# MakerBot.net
KiCad netlist of a schematic drawn in EAGLE
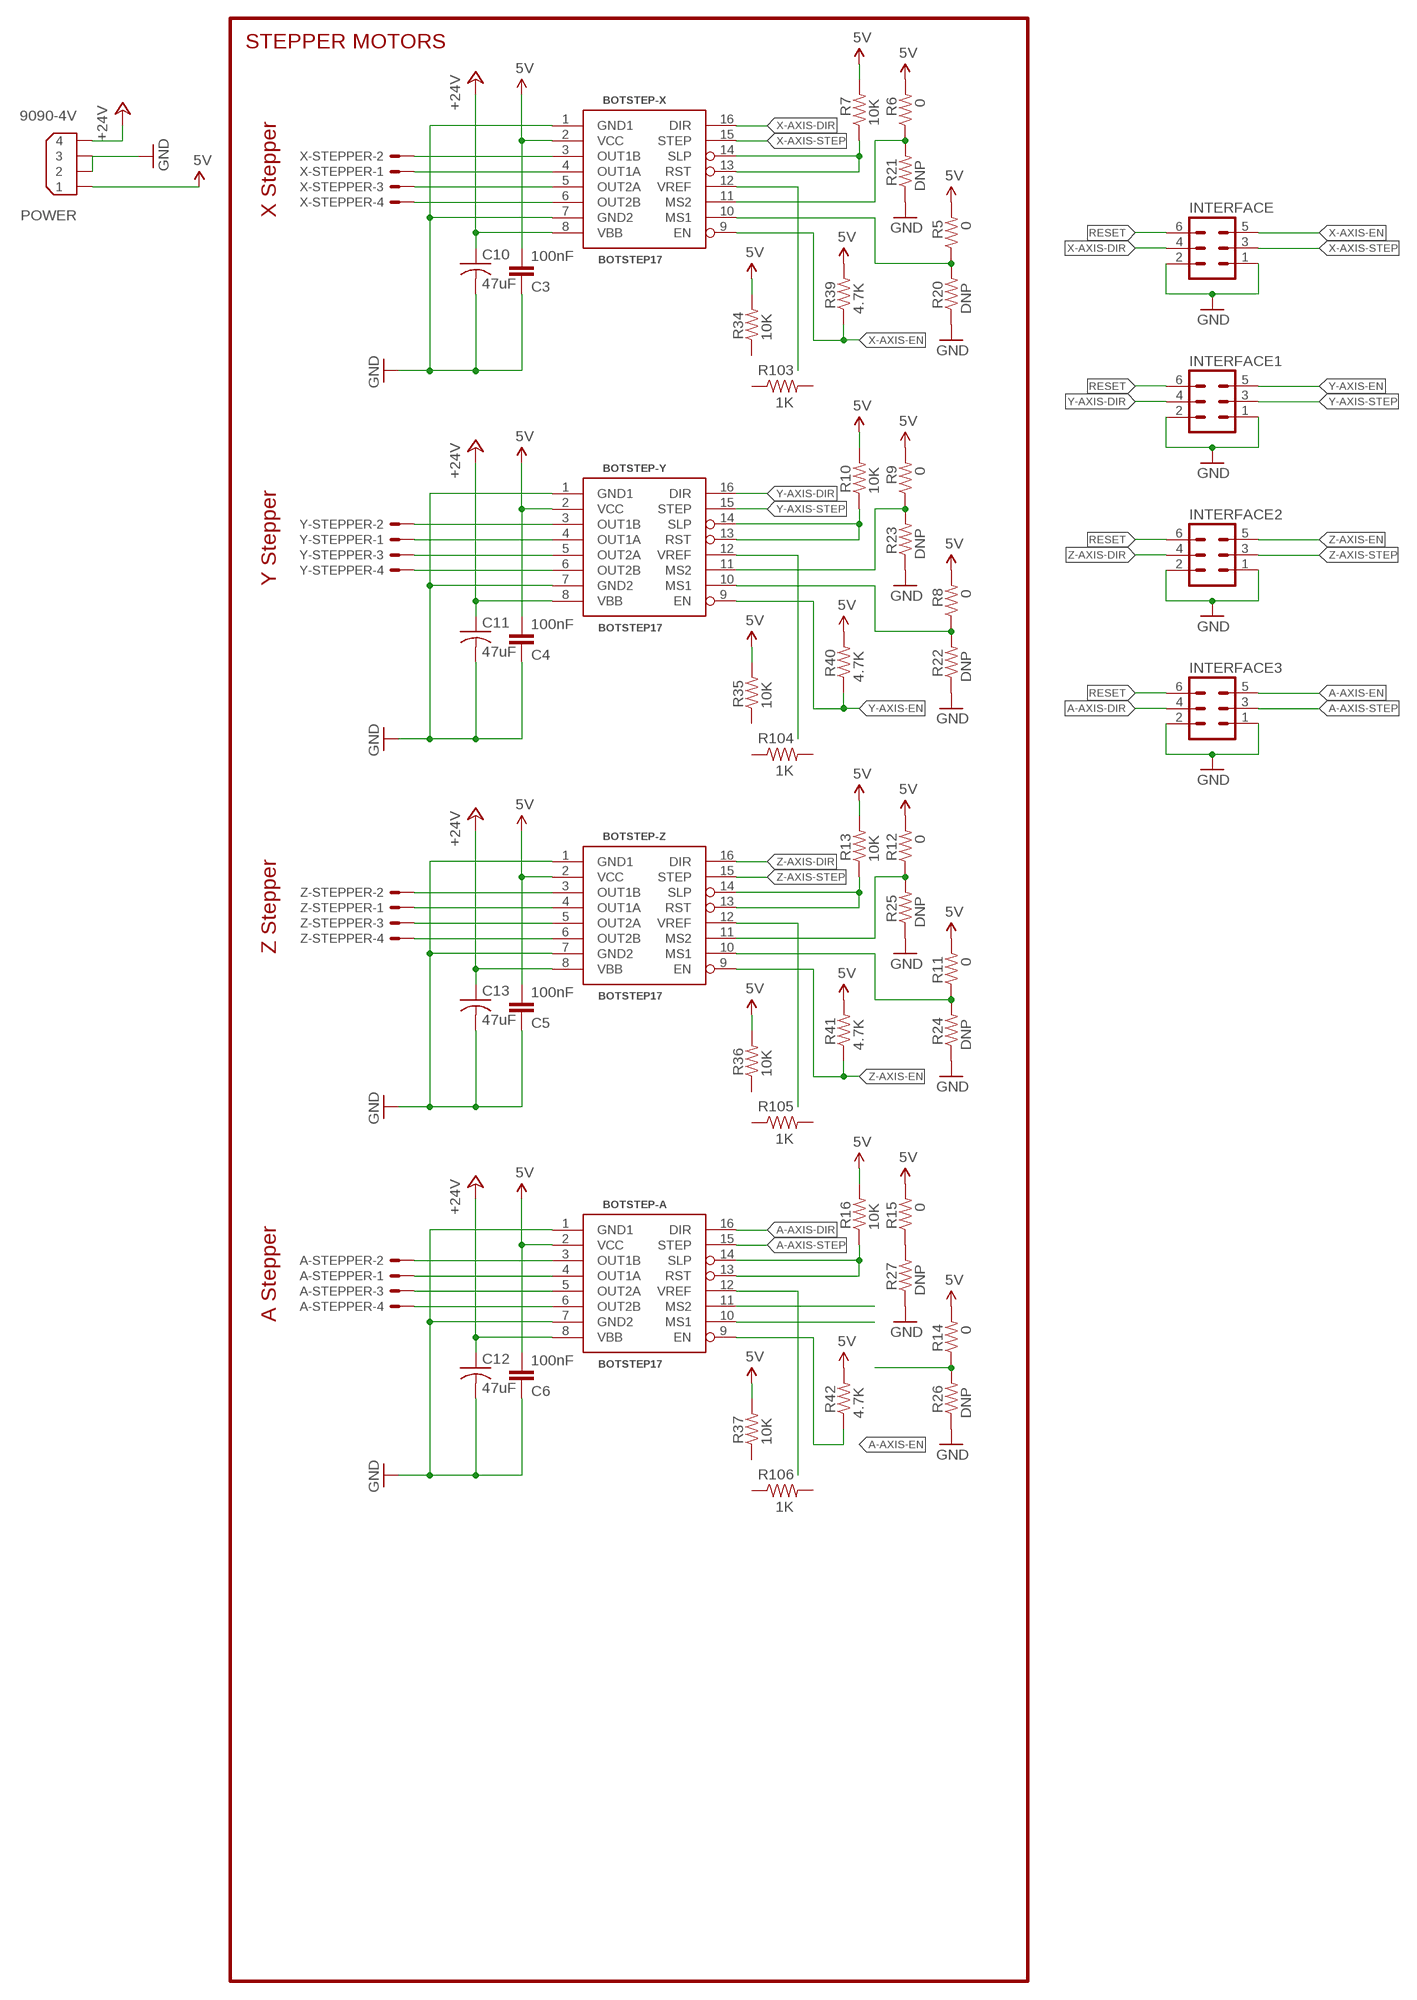
[diagram p0: schematic, sheet 1]

(export (version "E")
  (design (tool "Eeschema 10.0.6"))
  (components
    (comp (ref "A-STEPPER")
      (value "KK-156-4")
      (footprint "eagle-import:KK-156-4")
      (libsource (lib "eagle-import") (part "KK-156-4"))
    )
    (comp (ref "BOTSTEP-A")
      (value "BOTSTEP17")
      (footprint "eagle-import:BOTSTEP17-INV")
      (libsource (lib "eagle-import") (part "BOTSTEP17CHIP-DOWN"))
    )
    (comp (ref "BOTSTEP-X")
      (value "BOTSTEP17")
      (footprint "eagle-import:BOTSTEP17-INV")
      (libsource (lib "eagle-import") (part "BOTSTEP17CHIP-DOWN"))
    )
    (comp (ref "BOTSTEP-Y")
      (value "BOTSTEP17")
      (footprint "eagle-import:BOTSTEP17-INV")
      (libsource (lib "eagle-import") (part "BOTSTEP17CHIP-DOWN"))
    )
    (comp (ref "BOTSTEP-Z")
      (value "BOTSTEP17")
      (footprint "eagle-import:BOTSTEP17-INV")
      (libsource (lib "eagle-import") (part "BOTSTEP17CHIP-DOWN"))
    )
    (comp (ref "C3")
      (value "100nF")
      (footprint "eagle-import:0805")
      (libsource (lib "eagle-import") (part "CAP0805"))
    )
    (comp (ref "C4")
      (value "100nF")
      (footprint "eagle-import:0805")
      (libsource (lib "eagle-import") (part "CAP0805"))
    )
    (comp (ref "C5")
      (value "100nF")
      (footprint "eagle-import:0805")
      (libsource (lib "eagle-import") (part "CAP0805"))
    )
    (comp (ref "C6")
      (value "100nF")
      (footprint "eagle-import:0805")
      (libsource (lib "eagle-import") (part "CAP0805"))
    )
    (comp (ref "C10")
      (value "47uF")
      (footprint "eagle-import:C050-075X075")
      (libsource (lib "eagle-import") (part "C-US050-075X075"))
    )
    (comp (ref "C11")
      (value "47uF")
      (footprint "eagle-import:C050-075X075")
      (libsource (lib "eagle-import") (part "C-US050-075X075"))
    )
    (comp (ref "C12")
      (value "47uF")
      (footprint "eagle-import:C050-075X075")
      (libsource (lib "eagle-import") (part "C-US050-075X075"))
    )
    (comp (ref "C13")
      (value "47uF")
      (footprint "eagle-import:C050-075X075")
      (libsource (lib "eagle-import") (part "C-US050-075X075"))
    )
    (comp (ref "INTERFACE")
      (value "ML6")
      (footprint "eagle-import:ML6")
      (libsource (lib "eagle-import") (part "ML6"))
    )
    (comp (ref "INTERFACE1")
      (value "ML6")
      (footprint "eagle-import:ML6")
      (libsource (lib "eagle-import") (part "ML6"))
    )
    (comp (ref "INTERFACE2")
      (value "ML6")
      (footprint "eagle-import:ML6")
      (libsource (lib "eagle-import") (part "ML6"))
    )
    (comp (ref "INTERFACE3")
      (value "ML6")
      (footprint "eagle-import:ML6")
      (libsource (lib "eagle-import") (part "ML6"))
    )
    (comp (ref "POWER")
      (value "9090-4V")
      (footprint "eagle-import:9090-4V")
      (libsource (lib "eagle-import") (part "9090-4V"))
    )
    (comp (ref "R5")
      (value "0")
      (footprint "eagle-import:AXIAL-0.3")
      (libsource (lib "eagle-import") (part "RESISTORPTH1"))
    )
    (comp (ref "R6")
      (value "0")
      (footprint "eagle-import:AXIAL-0.3")
      (libsource (lib "eagle-import") (part "RESISTORPTH1"))
    )
    (comp (ref "R7")
      (value "10K")
      (footprint "eagle-import:AXIAL-0.3")
      (libsource (lib "eagle-import") (part "RESISTORPTH1"))
    )
    (comp (ref "R8")
      (value "0")
      (footprint "eagle-import:AXIAL-0.3")
      (libsource (lib "eagle-import") (part "RESISTORPTH1"))
    )
    (comp (ref "R9")
      (value "0")
      (footprint "eagle-import:AXIAL-0.3")
      (libsource (lib "eagle-import") (part "RESISTORPTH1"))
    )
    (comp (ref "R10")
      (value "10K")
      (footprint "eagle-import:AXIAL-0.3")
      (libsource (lib "eagle-import") (part "RESISTORPTH1"))
    )
    (comp (ref "R11")
      (value "0")
      (footprint "eagle-import:0805")
      (libsource (lib "eagle-import") (part "RESISTOR"))
    )
    (comp (ref "R12")
      (value "0")
      (footprint "eagle-import:0805")
      (libsource (lib "eagle-import") (part "RESISTOR"))
    )
    (comp (ref "R13")
      (value "10K")
      (footprint "eagle-import:0805")
      (libsource (lib "eagle-import") (part "RESISTOR"))
    )
    (comp (ref "R14")
      (value "0")
      (footprint "eagle-import:0805")
      (libsource (lib "eagle-import") (part "RESISTOR"))
    )
    (comp (ref "R15")
      (value "0")
      (footprint "eagle-import:0805")
      (libsource (lib "eagle-import") (part "RESISTOR"))
    )
    (comp (ref "R16")
      (value "10K")
      (footprint "eagle-import:0805")
      (libsource (lib "eagle-import") (part "RESISTOR"))
    )
    (comp (ref "R20")
      (value "DNP")
      (footprint "eagle-import:AXIAL-0.3")
      (libsource (lib "eagle-import") (part "RESISTORPTH1"))
    )
    (comp (ref "R21")
      (value "DNP")
      (footprint "eagle-import:AXIAL-0.3")
      (libsource (lib "eagle-import") (part "RESISTORPTH1"))
    )
    (comp (ref "R22")
      (value "DNP")
      (footprint "eagle-import:AXIAL-0.3")
      (libsource (lib "eagle-import") (part "RESISTORPTH1"))
    )
    (comp (ref "R23")
      (value "DNP")
      (footprint "eagle-import:AXIAL-0.3")
      (libsource (lib "eagle-import") (part "RESISTORPTH1"))
    )
    (comp (ref "R24")
      (value "DNP")
      (footprint "eagle-import:0805")
      (libsource (lib "eagle-import") (part "RESISTOR"))
    )
    (comp (ref "R25")
      (value "DNP")
      (footprint "eagle-import:0805")
      (libsource (lib "eagle-import") (part "RESISTOR"))
    )
    (comp (ref "R26")
      (value "DNP")
      (footprint "eagle-import:0805")
      (libsource (lib "eagle-import") (part "RESISTOR"))
    )
    (comp (ref "R27")
      (value "DNP")
      (footprint "eagle-import:0805")
      (libsource (lib "eagle-import") (part "RESISTOR"))
    )
    (comp (ref "R34")
      (value "10K")
      (footprint "eagle-import:AXIAL-0.3")
      (libsource (lib "eagle-import") (part "RESISTORPTH1"))
    )
    (comp (ref "R35")
      (value "10K")
      (footprint "eagle-import:AXIAL-0.3")
      (libsource (lib "eagle-import") (part "RESISTORPTH1"))
    )
    (comp (ref "R36")
      (value "10K")
      (footprint "eagle-import:0805")
      (libsource (lib "eagle-import") (part "RESISTOR"))
    )
    (comp (ref "R37")
      (value "10K")
      (footprint "eagle-import:0805")
      (libsource (lib "eagle-import") (part "RESISTOR"))
    )
    (comp (ref "R39")
      (value "4.7K")
      (footprint "eagle-import:AXIAL-0.3")
      (libsource (lib "eagle-import") (part "RESISTORPTH1"))
    )
    (comp (ref "R40")
      (value "4.7K")
      (footprint "eagle-import:AXIAL-0.3")
      (libsource (lib "eagle-import") (part "RESISTORPTH1"))
    )
    (comp (ref "R41")
      (value "4.7K")
      (footprint "eagle-import:0805")
      (libsource (lib "eagle-import") (part "RESISTOR"))
    )
    (comp (ref "R42")
      (value "4.7K")
      (footprint "eagle-import:0805")
      (libsource (lib "eagle-import") (part "RESISTOR"))
    )
    (comp (ref "R103")
      (value "1K")
      (footprint "eagle-import:AXIAL-0.3")
      (libsource (lib "eagle-import") (part "RESISTORPTH1"))
    )
    (comp (ref "R104")
      (value "1K")
      (footprint "eagle-import:AXIAL-0.3")
      (libsource (lib "eagle-import") (part "RESISTORPTH1"))
    )
    (comp (ref "R105")
      (value "1K")
      (footprint "eagle-import:0805")
      (libsource (lib "eagle-import") (part "RESISTOR"))
    )
    (comp (ref "R106")
      (value "1K")
      (footprint "eagle-import:0805")
      (libsource (lib "eagle-import") (part "RESISTOR"))
    )
    (comp (ref "X-STEPPER")
      (value "KK-156-4")
      (footprint "eagle-import:KK-156-4")
      (libsource (lib "eagle-import") (part "KK-156-4"))
    )
    (comp (ref "Y-STEPPER")
      (value "KK-156-4")
      (footprint "eagle-import:KK-156-4")
      (libsource (lib "eagle-import") (part "KK-156-4"))
    )
    (comp (ref "Z-STEPPER")
      (value "KK-156-4")
      (footprint "eagle-import:KK-156-4")
      (libsource (lib "eagle-import") (part "KK-156-4"))
    )
  )
  (nets
    (net (code "1") (name "+24V") (class "Default")
      (node (ref "BOTSTEP-A") (pin "8") (pinfunction "VBB_8") (pintype "bidirectional"))
      (node (ref "BOTSTEP-X") (pin "8") (pinfunction "VBB_8") (pintype "bidirectional"))
      (node (ref "BOTSTEP-Y") (pin "8") (pinfunction "VBB_8") (pintype "bidirectional"))
      (node (ref "BOTSTEP-Z") (pin "8") (pinfunction "VBB_8") (pintype "bidirectional"))
      (node (ref "C10") (pin "1") (pinfunction "1_1") (pintype "passive"))
      (node (ref "C11") (pin "1") (pinfunction "1_1") (pintype "passive"))
      (node (ref "C12") (pin "1") (pinfunction "1_1") (pintype "passive"))
      (node (ref "C13") (pin "1") (pinfunction "1_1") (pintype "passive"))
      (node (ref "POWER") (pin "4") (pinfunction "4_4") (pintype "passive"))
    )
    (net (code "2") (name "5V") (class "Default")
      (node (ref "BOTSTEP-A") (pin "2") (pinfunction "VCC_2") (pintype "bidirectional"))
      (node (ref "BOTSTEP-X") (pin "2") (pinfunction "VCC_2") (pintype "bidirectional"))
      (node (ref "BOTSTEP-Y") (pin "2") (pinfunction "VCC_2") (pintype "bidirectional"))
      (node (ref "BOTSTEP-Z") (pin "2") (pinfunction "VCC_2") (pintype "bidirectional"))
      (node (ref "C3") (pin "2") (pinfunction "2_2") (pintype "passive"))
      (node (ref "C4") (pin "2") (pinfunction "2_2") (pintype "passive"))
      (node (ref "C5") (pin "2") (pinfunction "2_2") (pintype "passive"))
      (node (ref "C6") (pin "2") (pinfunction "2_2") (pintype "passive"))
      (node (ref "POWER") (pin "1") (pinfunction "1_1") (pintype "passive"))
      (node (ref "R10") (pin "P$2") (pinfunction "2_P$2") (pintype "passive"))
      (node (ref "R11") (pin "2") (pinfunction "2_2") (pintype "passive"))
      (node (ref "R12") (pin "2") (pinfunction "2_2") (pintype "passive"))
      (node (ref "R13") (pin "2") (pinfunction "2_2") (pintype "passive"))
      (node (ref "R14") (pin "2") (pinfunction "2_2") (pintype "passive"))
      (node (ref "R15") (pin "2") (pinfunction "2_2") (pintype "passive"))
      (node (ref "R16") (pin "2") (pinfunction "2_2") (pintype "passive"))
      (node (ref "R34") (pin "P$2") (pinfunction "2_P$2") (pintype "passive"))
      (node (ref "R35") (pin "P$2") (pinfunction "2_P$2") (pintype "passive"))
      (node (ref "R36") (pin "2") (pinfunction "2_2") (pintype "passive"))
      (node (ref "R37") (pin "2") (pinfunction "2_2") (pintype "passive"))
      (node (ref "R39") (pin "P$2") (pinfunction "2_P$2") (pintype "passive"))
      (node (ref "R40") (pin "P$2") (pinfunction "2_P$2") (pintype "passive"))
      (node (ref "R41") (pin "2") (pinfunction "2_2") (pintype "passive"))
      (node (ref "R42") (pin "2") (pinfunction "2_2") (pintype "passive"))
      (node (ref "R5") (pin "P$2") (pinfunction "2_P$2") (pintype "passive"))
      (node (ref "R6") (pin "P$2") (pinfunction "2_P$2") (pintype "passive"))
      (node (ref "R7") (pin "P$2") (pinfunction "2_P$2") (pintype "passive"))
      (node (ref "R8") (pin "P$2") (pinfunction "2_P$2") (pintype "passive"))
      (node (ref "R9") (pin "P$2") (pinfunction "2_P$2") (pintype "passive"))
    )
    (net (code "3") (name "A-AXIS-DIR") (class "Default")
      (node (ref "BOTSTEP-A") (pin "16") (pinfunction "DIR_16") (pintype "input"))
      (node (ref "INTERFACE3") (pin "4") (pinfunction "4_4") (pintype "passive"))
    )
    (net (code "4") (name "A-AXIS-EN") (class "Default")
      (node (ref "BOTSTEP-A") (pin "9") (pinfunction "EN_9") (pintype "input"))
      (node (ref "INTERFACE3") (pin "5") (pinfunction "5_5") (pintype "passive"))
      (node (ref "R42") (pin "1") (pinfunction "1_1") (pintype "passive"))
    )
    (net (code "5") (name "A-AXIS-STEP") (class "Default")
      (node (ref "BOTSTEP-A") (pin "15") (pinfunction "STEP_15") (pintype "input"))
      (node (ref "INTERFACE3") (pin "3") (pinfunction "3_3") (pintype "passive"))
    )
    (net (code "6") (name "GND") (class "Default")
      (node (ref "BOTSTEP-A") (pin "1") (pinfunction "GND1_1") (pintype "bidirectional"))
      (node (ref "BOTSTEP-A") (pin "7") (pinfunction "GND2_7") (pintype "bidirectional"))
      (node (ref "BOTSTEP-X") (pin "1") (pinfunction "GND1_1") (pintype "bidirectional"))
      (node (ref "BOTSTEP-X") (pin "7") (pinfunction "GND2_7") (pintype "bidirectional"))
      (node (ref "BOTSTEP-Y") (pin "1") (pinfunction "GND1_1") (pintype "bidirectional"))
      (node (ref "BOTSTEP-Y") (pin "7") (pinfunction "GND2_7") (pintype "bidirectional"))
      (node (ref "BOTSTEP-Z") (pin "1") (pinfunction "GND1_1") (pintype "bidirectional"))
      (node (ref "BOTSTEP-Z") (pin "7") (pinfunction "GND2_7") (pintype "bidirectional"))
      (node (ref "C10") (pin "2") (pinfunction "2_2") (pintype "passive"))
      (node (ref "C11") (pin "2") (pinfunction "2_2") (pintype "passive"))
      (node (ref "C12") (pin "2") (pinfunction "2_2") (pintype "passive"))
      (node (ref "C13") (pin "2") (pinfunction "2_2") (pintype "passive"))
      (node (ref "C3") (pin "1") (pinfunction "1_1") (pintype "passive"))
      (node (ref "C4") (pin "1") (pinfunction "1_1") (pintype "passive"))
      (node (ref "C5") (pin "1") (pinfunction "1_1") (pintype "passive"))
      (node (ref "C6") (pin "1") (pinfunction "1_1") (pintype "passive"))
      (node (ref "INTERFACE") (pin "1") (pinfunction "1_1") (pintype "passive"))
      (node (ref "INTERFACE") (pin "2") (pinfunction "2_2") (pintype "passive"))
      (node (ref "INTERFACE1") (pin "1") (pinfunction "1_1") (pintype "passive"))
      (node (ref "INTERFACE1") (pin "2") (pinfunction "2_2") (pintype "passive"))
      (node (ref "INTERFACE2") (pin "1") (pinfunction "1_1") (pintype "passive"))
      (node (ref "INTERFACE2") (pin "2") (pinfunction "2_2") (pintype "passive"))
      (node (ref "INTERFACE3") (pin "1") (pinfunction "1_1") (pintype "passive"))
      (node (ref "INTERFACE3") (pin "2") (pinfunction "2_2") (pintype "passive"))
      (node (ref "POWER") (pin "2") (pinfunction "2_2") (pintype "passive"))
      (node (ref "POWER") (pin "3") (pinfunction "3_3") (pintype "passive"))
      (node (ref "R20") (pin "P$1") (pinfunction "1_P$1") (pintype "passive"))
      (node (ref "R21") (pin "P$1") (pinfunction "1_P$1") (pintype "passive"))
      (node (ref "R22") (pin "P$1") (pinfunction "1_P$1") (pintype "passive"))
      (node (ref "R23") (pin "P$1") (pinfunction "1_P$1") (pintype "passive"))
      (node (ref "R24") (pin "1") (pinfunction "1_1") (pintype "passive"))
      (node (ref "R25") (pin "1") (pinfunction "1_1") (pintype "passive"))
      (node (ref "R26") (pin "1") (pinfunction "1_1") (pintype "passive"))
      (node (ref "R27") (pin "1") (pinfunction "1_1") (pintype "passive"))
    )
    (net (code "7") (name "Net-(A-STEPPERA-S)") (class "Default")
      (node (ref "A-STEPPER") (pin "1") (pinfunction "S_1") (pintype "passive"))
      (node (ref "BOTSTEP-A") (pin "4") (pinfunction "OUT1A_4") (pintype "output"))
    )
    (net (code "8") (name "Net-(A-STEPPERB-S)") (class "Default")
      (node (ref "A-STEPPER") (pin "2") (pinfunction "S_2") (pintype "passive"))
      (node (ref "BOTSTEP-A") (pin "3") (pinfunction "OUT1B_3") (pintype "output"))
    )
    (net (code "9") (name "Net-(A-STEPPERC-S)") (class "Default")
      (node (ref "A-STEPPER") (pin "3") (pinfunction "S_3") (pintype "passive"))
      (node (ref "BOTSTEP-A") (pin "5") (pinfunction "OUT2A_5") (pintype "output"))
    )
    (net (code "10") (name "Net-(A-STEPPERD-S)") (class "Default")
      (node (ref "A-STEPPER") (pin "4") (pinfunction "S_4") (pintype "passive"))
      (node (ref "BOTSTEP-A") (pin "6") (pinfunction "OUT2B_6") (pintype "output"))
    )
    (net (code "11") (name "Net-(BOTSTEP-A-RST)") (class "Default")
      (node (ref "BOTSTEP-A") (pin "13") (pinfunction "RST_13") (pintype "input"))
      (node (ref "BOTSTEP-A") (pin "14") (pinfunction "SLP_14") (pintype "input"))
      (node (ref "R16") (pin "1") (pinfunction "1_1") (pintype "passive"))
    )
    (net (code "12") (name "Net-(BOTSTEP-X-MS1)") (class "Default")
      (node (ref "BOTSTEP-X") (pin "10") (pinfunction "MS1_10") (pintype "input"))
      (node (ref "R20") (pin "P$2") (pinfunction "2_P$2") (pintype "passive"))
      (node (ref "R5") (pin "P$1") (pinfunction "1_P$1") (pintype "passive"))
    )
    (net (code "13") (name "Net-(BOTSTEP-X-MS2)") (class "Default")
      (node (ref "BOTSTEP-X") (pin "11") (pinfunction "MS2_11") (pintype "input"))
      (node (ref "R21") (pin "P$2") (pinfunction "2_P$2") (pintype "passive"))
      (node (ref "R6") (pin "P$1") (pinfunction "1_P$1") (pintype "passive"))
    )
    (net (code "14") (name "Net-(BOTSTEP-X-OUT1A)") (class "Default")
      (node (ref "BOTSTEP-X") (pin "4") (pinfunction "OUT1A_4") (pintype "output"))
      (node (ref "X-STEPPER") (pin "1") (pinfunction "S_1") (pintype "passive"))
    )
    (net (code "15") (name "Net-(BOTSTEP-X-OUT1B)") (class "Default")
      (node (ref "BOTSTEP-X") (pin "3") (pinfunction "OUT1B_3") (pintype "output"))
      (node (ref "X-STEPPER") (pin "2") (pinfunction "S_2") (pintype "passive"))
    )
    (net (code "16") (name "Net-(BOTSTEP-X-OUT2A)") (class "Default")
      (node (ref "BOTSTEP-X") (pin "5") (pinfunction "OUT2A_5") (pintype "output"))
      (node (ref "X-STEPPER") (pin "3") (pinfunction "S_3") (pintype "passive"))
    )
    (net (code "17") (name "Net-(BOTSTEP-X-OUT2B)") (class "Default")
      (node (ref "BOTSTEP-X") (pin "6") (pinfunction "OUT2B_6") (pintype "output"))
      (node (ref "X-STEPPER") (pin "4") (pinfunction "S_4") (pintype "passive"))
    )
    (net (code "18") (name "Net-(BOTSTEP-X-RST)") (class "Default")
      (node (ref "BOTSTEP-X") (pin "13") (pinfunction "RST_13") (pintype "input"))
      (node (ref "BOTSTEP-X") (pin "14") (pinfunction "SLP_14") (pintype "input"))
      (node (ref "R7") (pin "P$1") (pinfunction "1_P$1") (pintype "passive"))
    )
    (net (code "19") (name "Net-(BOTSTEP-Y-MS1)") (class "Default")
      (node (ref "BOTSTEP-Y") (pin "10") (pinfunction "MS1_10") (pintype "input"))
      (node (ref "R22") (pin "P$2") (pinfunction "2_P$2") (pintype "passive"))
      (node (ref "R8") (pin "P$1") (pinfunction "1_P$1") (pintype "passive"))
    )
    (net (code "20") (name "Net-(BOTSTEP-Y-MS2)") (class "Default")
      (node (ref "BOTSTEP-Y") (pin "11") (pinfunction "MS2_11") (pintype "input"))
      (node (ref "R23") (pin "P$2") (pinfunction "2_P$2") (pintype "passive"))
      (node (ref "R9") (pin "P$1") (pinfunction "1_P$1") (pintype "passive"))
    )
    (net (code "21") (name "Net-(BOTSTEP-Y-OUT1A)") (class "Default")
      (node (ref "BOTSTEP-Y") (pin "4") (pinfunction "OUT1A_4") (pintype "output"))
      (node (ref "Y-STEPPER") (pin "1") (pinfunction "S_1") (pintype "passive"))
    )
    (net (code "22") (name "Net-(BOTSTEP-Y-OUT1B)") (class "Default")
      (node (ref "BOTSTEP-Y") (pin "3") (pinfunction "OUT1B_3") (pintype "output"))
      (node (ref "Y-STEPPER") (pin "2") (pinfunction "S_2") (pintype "passive"))
    )
    (net (code "23") (name "Net-(BOTSTEP-Y-OUT2A)") (class "Default")
      (node (ref "BOTSTEP-Y") (pin "5") (pinfunction "OUT2A_5") (pintype "output"))
      (node (ref "Y-STEPPER") (pin "3") (pinfunction "S_3") (pintype "passive"))
    )
    (net (code "24") (name "Net-(BOTSTEP-Y-OUT2B)") (class "Default")
      (node (ref "BOTSTEP-Y") (pin "6") (pinfunction "OUT2B_6") (pintype "output"))
      (node (ref "Y-STEPPER") (pin "4") (pinfunction "S_4") (pintype "passive"))
    )
    (net (code "25") (name "Net-(BOTSTEP-Y-RST)") (class "Default")
      (node (ref "BOTSTEP-Y") (pin "13") (pinfunction "RST_13") (pintype "input"))
      (node (ref "BOTSTEP-Y") (pin "14") (pinfunction "SLP_14") (pintype "input"))
      (node (ref "R10") (pin "P$1") (pinfunction "1_P$1") (pintype "passive"))
    )
    (net (code "26") (name "Net-(BOTSTEP-Z-MS1)") (class "Default")
      (node (ref "BOTSTEP-Z") (pin "10") (pinfunction "MS1_10") (pintype "input"))
      (node (ref "R11") (pin "1") (pinfunction "1_1") (pintype "passive"))
      (node (ref "R24") (pin "2") (pinfunction "2_2") (pintype "passive"))
    )
    (net (code "27") (name "Net-(BOTSTEP-Z-MS2)") (class "Default")
      (node (ref "BOTSTEP-Z") (pin "11") (pinfunction "MS2_11") (pintype "input"))
      (node (ref "R12") (pin "1") (pinfunction "1_1") (pintype "passive"))
      (node (ref "R25") (pin "2") (pinfunction "2_2") (pintype "passive"))
    )
    (net (code "28") (name "Net-(BOTSTEP-Z-OUT1A)") (class "Default")
      (node (ref "BOTSTEP-Z") (pin "4") (pinfunction "OUT1A_4") (pintype "output"))
      (node (ref "Z-STEPPER") (pin "1") (pinfunction "S_1") (pintype "passive"))
    )
    (net (code "29") (name "Net-(BOTSTEP-Z-OUT1B)") (class "Default")
      (node (ref "BOTSTEP-Z") (pin "3") (pinfunction "OUT1B_3") (pintype "output"))
      (node (ref "Z-STEPPER") (pin "2") (pinfunction "S_2") (pintype "passive"))
    )
    (net (code "30") (name "Net-(BOTSTEP-Z-OUT2A)") (class "Default")
      (node (ref "BOTSTEP-Z") (pin "5") (pinfunction "OUT2A_5") (pintype "output"))
      (node (ref "Z-STEPPER") (pin "3") (pinfunction "S_3") (pintype "passive"))
    )
    (net (code "31") (name "Net-(BOTSTEP-Z-OUT2B)") (class "Default")
      (node (ref "BOTSTEP-Z") (pin "6") (pinfunction "OUT2B_6") (pintype "output"))
      (node (ref "Z-STEPPER") (pin "4") (pinfunction "S_4") (pintype "passive"))
    )
    (net (code "32") (name "Net-(BOTSTEP-Z-RST)") (class "Default")
      (node (ref "BOTSTEP-Z") (pin "13") (pinfunction "RST_13") (pintype "input"))
      (node (ref "BOTSTEP-Z") (pin "14") (pinfunction "SLP_14") (pintype "input"))
      (node (ref "R13") (pin "1") (pinfunction "1_1") (pintype "passive"))
    )
    (net (code "33") (name "Net-(R14-Pad1)") (class "Default")
      (node (ref "R14") (pin "1") (pinfunction "1_1") (pintype "passive"))
      (node (ref "R26") (pin "2") (pinfunction "2_2") (pintype "passive"))
    )
    (net (code "34") (name "Net-(R15-Pad1)") (class "Default")
      (node (ref "R15") (pin "1") (pinfunction "1_1") (pintype "passive"))
      (node (ref "R27") (pin "2") (pinfunction "2_2") (pintype "passive"))
    )
    (net (code "35") (name "RESET") (class "Default")
      (node (ref "INTERFACE") (pin "6") (pinfunction "6_6") (pintype "passive"))
      (node (ref "INTERFACE1") (pin "6") (pinfunction "6_6") (pintype "passive"))
      (node (ref "INTERFACE2") (pin "6") (pinfunction "6_6") (pintype "passive"))
      (node (ref "INTERFACE3") (pin "6") (pinfunction "6_6") (pintype "passive"))
    )
    (net (code "36") (name "X-AXIS-DIR") (class "Default")
      (node (ref "BOTSTEP-X") (pin "16") (pinfunction "DIR_16") (pintype "input"))
      (node (ref "INTERFACE") (pin "4") (pinfunction "4_4") (pintype "passive"))
    )
    (net (code "37") (name "X-AXIS-EN") (class "Default")
      (node (ref "BOTSTEP-X") (pin "9") (pinfunction "EN_9") (pintype "input"))
      (node (ref "INTERFACE") (pin "5") (pinfunction "5_5") (pintype "passive"))
      (node (ref "R39") (pin "P$1") (pinfunction "1_P$1") (pintype "passive"))
    )
    (net (code "38") (name "X-AXIS-STEP") (class "Default")
      (node (ref "BOTSTEP-X") (pin "15") (pinfunction "STEP_15") (pintype "input"))
      (node (ref "INTERFACE") (pin "3") (pinfunction "3_3") (pintype "passive"))
    )
    (net (code "39") (name "Y-AXIS-DIR") (class "Default")
      (node (ref "BOTSTEP-Y") (pin "16") (pinfunction "DIR_16") (pintype "input"))
      (node (ref "INTERFACE1") (pin "4") (pinfunction "4_4") (pintype "passive"))
    )
    (net (code "40") (name "Y-AXIS-EN") (class "Default")
      (node (ref "BOTSTEP-Y") (pin "9") (pinfunction "EN_9") (pintype "input"))
      (node (ref "INTERFACE1") (pin "5") (pinfunction "5_5") (pintype "passive"))
      (node (ref "R40") (pin "P$1") (pinfunction "1_P$1") (pintype "passive"))
    )
    (net (code "41") (name "Y-AXIS-STEP") (class "Default")
      (node (ref "BOTSTEP-Y") (pin "15") (pinfunction "STEP_15") (pintype "input"))
      (node (ref "INTERFACE1") (pin "3") (pinfunction "3_3") (pintype "passive"))
    )
    (net (code "42") (name "Z-AXIS-DIR") (class "Default")
      (node (ref "BOTSTEP-Z") (pin "16") (pinfunction "DIR_16") (pintype "input"))
      (node (ref "INTERFACE2") (pin "4") (pinfunction "4_4") (pintype "passive"))
    )
    (net (code "43") (name "Z-AXIS-EN") (class "Default")
      (node (ref "BOTSTEP-Z") (pin "9") (pinfunction "EN_9") (pintype "input"))
      (node (ref "INTERFACE2") (pin "5") (pinfunction "5_5") (pintype "passive"))
      (node (ref "R41") (pin "1") (pinfunction "1_1") (pintype "passive"))
    )
    (net (code "44") (name "Z-AXIS-STEP") (class "Default")
      (node (ref "BOTSTEP-Z") (pin "15") (pinfunction "STEP_15") (pintype "input"))
      (node (ref "INTERFACE2") (pin "3") (pinfunction "3_3") (pintype "passive"))
    )
    (net (code "45") (name "unconnected-(BOTSTEP-A-MS1-Pad10)") (class "Default")
      (node (ref "BOTSTEP-A") (pin "10") (pinfunction "MS1_10") (pintype "input"))
    )
    (net (code "46") (name "unconnected-(BOTSTEP-A-MS2-Pad11)") (class "Default")
      (node (ref "BOTSTEP-A") (pin "11") (pinfunction "MS2_11") (pintype "input"))
    )
    (net (code "47") (name "unconnected-(BOTSTEP-A-VREF-Pad12)") (class "Default")
      (node (ref "BOTSTEP-A") (pin "12") (pinfunction "VREF_12") (pintype "input"))
    )
    (net (code "48") (name "unconnected-(BOTSTEP-X-VREF-Pad12)") (class "Default")
      (node (ref "BOTSTEP-X") (pin "12") (pinfunction "VREF_12") (pintype "input"))
    )
    (net (code "49") (name "unconnected-(BOTSTEP-Y-VREF-Pad12)") (class "Default")
      (node (ref "BOTSTEP-Y") (pin "12") (pinfunction "VREF_12") (pintype "input"))
    )
    (net (code "50") (name "unconnected-(BOTSTEP-Z-VREF-Pad12)") (class "Default")
      (node (ref "BOTSTEP-Z") (pin "12") (pinfunction "VREF_12") (pintype "input"))
    )
    (net (code "51") (name "unconnected-(R34-1-PadP$1)") (class "Default")
      (node (ref "R34") (pin "P$1") (pinfunction "1_P$1") (pintype "passive"))
    )
    (net (code "52") (name "unconnected-(R35-1-PadP$1)") (class "Default")
      (node (ref "R35") (pin "P$1") (pinfunction "1_P$1") (pintype "passive"))
    )
    (net (code "53") (name "unconnected-(R36-Pad1)") (class "Default")
      (node (ref "R36") (pin "1") (pinfunction "1_1") (pintype "passive"))
    )
    (net (code "54") (name "unconnected-(R37-Pad1)") (class "Default")
      (node (ref "R37") (pin "1") (pinfunction "1_1") (pintype "passive"))
    )
    (net (code "55") (name "unconnected-(R103-1-PadP$1)") (class "Default")
      (node (ref "R103") (pin "P$1") (pinfunction "1_P$1") (pintype "passive"))
    )
    (net (code "56") (name "unconnected-(R103-2-PadP$2)") (class "Default")
      (node (ref "R103") (pin "P$2") (pinfunction "2_P$2") (pintype "passive"))
    )
    (net (code "57") (name "unconnected-(R104-1-PadP$1)") (class "Default")
      (node (ref "R104") (pin "P$1") (pinfunction "1_P$1") (pintype "passive"))
    )
    (net (code "58") (name "unconnected-(R104-2-PadP$2)") (class "Default")
      (node (ref "R104") (pin "P$2") (pinfunction "2_P$2") (pintype "passive"))
    )
    (net (code "59") (name "unconnected-(R105-Pad1)") (class "Default")
      (node (ref "R105") (pin "1") (pinfunction "1_1") (pintype "passive"))
    )
    (net (code "60") (name "unconnected-(R105-Pad2)") (class "Default")
      (node (ref "R105") (pin "2") (pinfunction "2_2") (pintype "passive"))
    )
    (net (code "61") (name "unconnected-(R106-Pad1)") (class "Default")
      (node (ref "R106") (pin "1") (pinfunction "1_1") (pintype "passive"))
    )
    (net (code "62") (name "unconnected-(R106-Pad2)") (class "Default")
      (node (ref "R106") (pin "2") (pinfunction "2_2") (pintype "passive"))
    )
  )
)
